# Hall_Switch.net
KiCad netlist of a schematic drawn in EAGLE
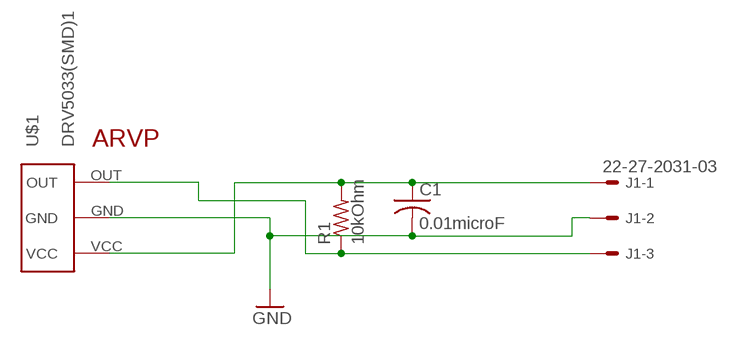
[diagram p0: schematic, sheet 1]

(export (version "E")
  (design (tool "Eeschema 10.0.6"))
  (components
    (comp (ref "C1")
      (value "0.01microF")
      (footprint "eagle-import:C2012")
      (libsource (lib "eagle-import") (part "C-USC2012"))
    )
    (comp (ref "J1")
      (value "22-27-2031-03")
      (footprint "eagle-import:6410-03")
      (libsource (lib "eagle-import") (part "22-?-0327-2031"))
    )
    (comp (ref "R1")
      (value "10kOhm")
      (footprint "eagle-import:M2012")
      (libsource (lib "eagle-import") (part "R-US_M2012"))
    )
    (comp (ref "U$1")
      (value "DRV5033(SMD)1")
      (footprint "eagle-import:SOT-23")
      (libsource (lib "eagle-import") (part "DRV5033(SMD)1"))
    )
    (comp (ref "U$2")
      (value "ARVP_LOGO")
      (footprint "eagle-import:ARVP")
      (libsource (lib "eagle-import") (part "ARVP_LOGO"))
    )
  )
  (nets
    (net (code "1") (name "GND") (class "Default")
      (node (ref "C1") (pin "2") (pinfunction "2_2") (pintype "passive"))
      (node (ref "J1") (pin "2") (pinfunction "S_2") (pintype "passive"))
      (node (ref "U$1") (pin "GND") (pinfunction "GND_GND") (pintype "power_in"))
    )
    (net (code "2") (name "Net-(J1A-S)") (class "Default")
      (node (ref "C1") (pin "1") (pinfunction "1_1") (pintype "passive"))
      (node (ref "J1") (pin "1") (pinfunction "S_1") (pintype "passive"))
      (node (ref "R1") (pin "2") (pinfunction "2_2") (pintype "passive"))
      (node (ref "U$1") (pin "VCC") (pinfunction "VCC_VCC") (pintype "power_in"))
    )
    (net (code "3") (name "Net-(J1C-S)") (class "Default")
      (node (ref "J1") (pin "3") (pinfunction "S_3") (pintype "passive"))
      (node (ref "R1") (pin "1") (pinfunction "1_1") (pintype "passive"))
      (node (ref "U$1") (pin "OUT") (pinfunction "OUT_OUT") (pintype "output"))
    )
  )
)
